# Qwiic-OpenLog.net
KiCad netlist of a schematic drawn in EAGLE
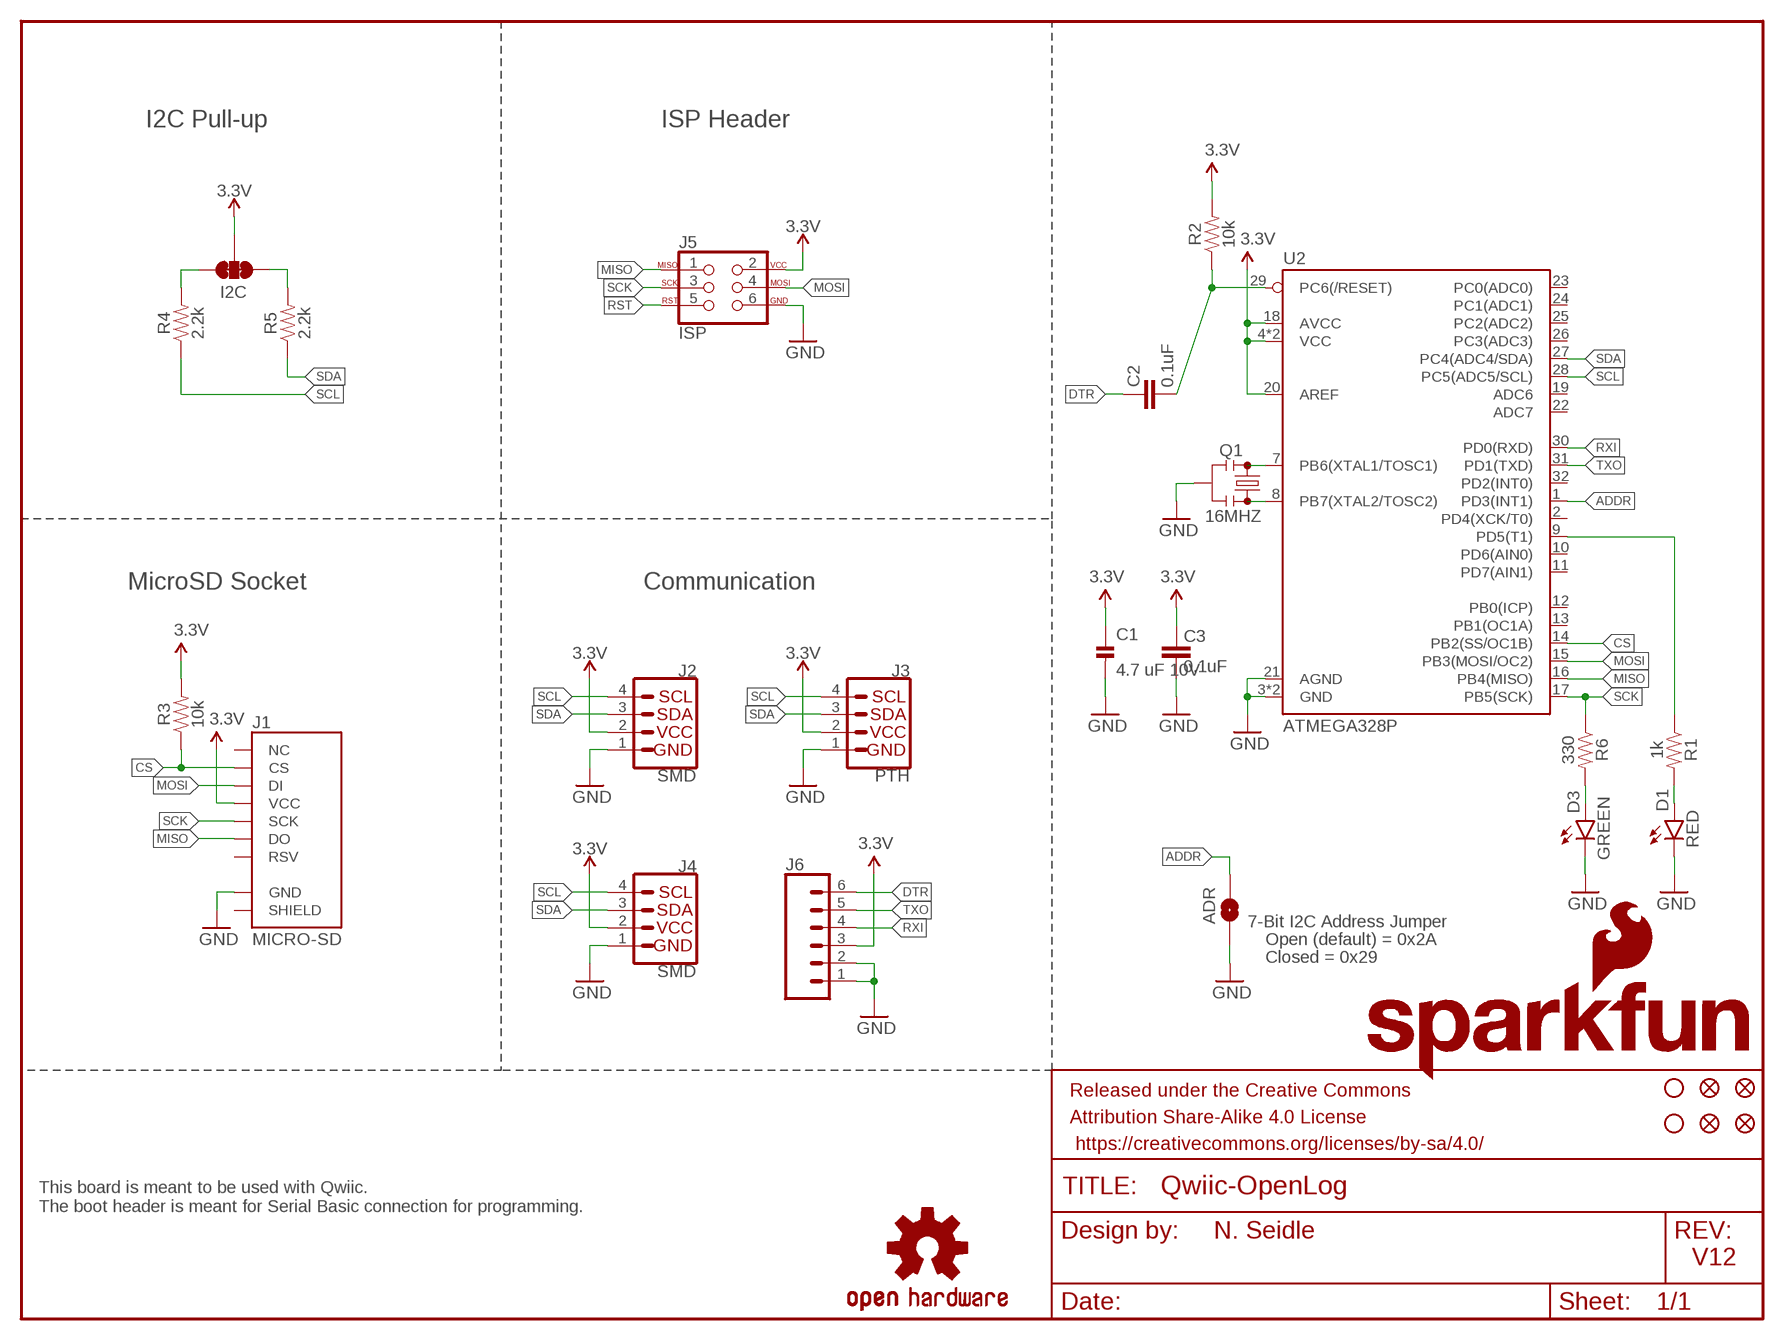
[diagram p0: schematic, sheet 1]

(export (version "E")
  (design (tool "Eeschema 10.0.6"))
  (components
    (comp (ref "ADR")
      (value "SOLDERJUMPERNO")
      (footprint "eagle-import:SJ_2S-NO")
      (libsource (lib "eagle-import") (part "SOLDERJUMPERNO"))
    )
    (comp (ref "C1")
      (value "4.7 uF 10V")
      (footprint "eagle-import:C0805")
      (fields (field (name "MANUFACTURER") "KEMET") (field (name "MPN") "C0805C475J8RACAUTO"))
      (libsource (lib "eagle-import") (part "C0805C475J8RACAUTO"))
    )
    (comp (ref "C2")
      (value "0.1uF")
      (footprint "eagle-import:0603")
      (libsource (lib "eagle-import") (part "0.1UF-0603-25V-(+80/-20%)"))
    )
    (comp (ref "C3")
      (value "0.1uF")
      (footprint "eagle-import:0603")
      (libsource (lib "eagle-import") (part "0.1UF-0603-25V-(+80/-20%)"))
    )
    (comp (ref "D1")
      (value "RED")
      (footprint "eagle-import:LED-0603")
      (libsource (lib "eagle-import") (part "LED-RED0603"))
    )
    (comp (ref "D3")
      (value "GREEN")
      (footprint "eagle-import:LED-0603")
      (libsource (lib "eagle-import") (part "LED-GREEN0603"))
    )
    (comp (ref "FID1")
      (value "FIDUCIALUFIDUCIAL")
      (footprint "eagle-import:FIDUCIAL-MICRO")
      (libsource (lib "eagle-import") (part "FIDUCIALUFIDUCIAL"))
    )
    (comp (ref "FID2")
      (value "FIDUCIALUFIDUCIAL")
      (footprint "eagle-import:FIDUCIAL-MICRO")
      (libsource (lib "eagle-import") (part "FIDUCIALUFIDUCIAL"))
    )
    (comp (ref "FID3")
      (value "FIDUCIALUFIDUCIAL")
      (footprint "eagle-import:FIDUCIAL-MICRO")
      (libsource (lib "eagle-import") (part "FIDUCIALUFIDUCIAL"))
    )
    (comp (ref "FID4")
      (value "FIDUCIALUFIDUCIAL")
      (footprint "eagle-import:FIDUCIAL-MICRO")
      (libsource (lib "eagle-import") (part "FIDUCIALUFIDUCIAL"))
    )
    (comp (ref "FRAME1")
      (value "FRAME-LETTER")
      (footprint "eagle-import:CREATIVE_COMMONS")
      (libsource (lib "eagle-import") (part "FRAME-LETTER"))
    )
    (comp (ref "I2C")
      (value "JUMPER-SMT_3_2-NC_TRACE_SILK")
      (footprint "eagle-import:SMT-JUMPER_3_2-NC_TRACE_SILK")
      (libsource (lib "eagle-import") (part "JUMPER-SMT_3_2-NC_TRACE_SILK"))
    )
    (comp (ref "J1")
      (value "MICRO-SD")
      (footprint "eagle-import:MICRO-SD-SOCKET")
      (libsource (lib "eagle-import") (part "MICRO-SD_CARD_SOCKETPUSH-PUSH"))
    )
    (comp (ref "J2")
      (value "SMD")
      (footprint "eagle-import:1X04_1MM_RA")
      (libsource (lib "eagle-import") (part "QWIIC_CONNECTORJS-1MM"))
    )
    (comp (ref "J3")
      (value "PTH")
      (footprint "eagle-import:1X04_NO_SILK")
      (libsource (lib "eagle-import") (part "I2C_STANDARD_NO_SILK"))
    )
    (comp (ref "J4")
      (value "SMD")
      (footprint "eagle-import:1X04_1MM_RA")
      (libsource (lib "eagle-import") (part "QWIIC_CONNECTORJS-1MM"))
    )
    (comp (ref "J5")
      (value "ISP")
      (footprint "eagle-import:2X3_TEST_POINTS")
      (libsource (lib "eagle-import") (part "AVR_SPI_PROG_3X2TESTPOINTS"))
    )
    (comp (ref "J6")
      (value "CONN_06NO_SILK_NO_POP")
      (footprint "eagle-import:1X06_NO_SILK")
      (libsource (lib "eagle-import") (part "CONN_06NO_SILK_NO_POP"))
    )
    (comp (ref "JP3")
      (value "STAND-OFF")
      (footprint "eagle-import:STAND-OFF")
      (libsource (lib "eagle-import") (part "STAND-OFF"))
    )
    (comp (ref "JP4")
      (value "STAND-OFF")
      (footprint "eagle-import:STAND-OFF")
      (libsource (lib "eagle-import") (part "STAND-OFF"))
    )
    (comp (ref "LOGO1")
      (value "SFE_LOGO_FLAME.1_INCH")
      (footprint "eagle-import:SFE_LOGO_FLAME_.1")
      (libsource (lib "eagle-import") (part "SFE_LOGO_FLAME.1_INCH"))
    )
    (comp (ref "LOGO2")
      (value "OSHW-LOGOMINI")
      (footprint "eagle-import:OSHW-LOGO-MINI")
      (libsource (lib "eagle-import") (part "OSHW-LOGOMINI"))
    )
    (comp (ref "LOGO4")
      (value "SFE_LOGO_NAME_FLAME.1_INCH")
      (footprint "eagle-import:SFE_LOGO_NAME_FLAME_.1")
      (libsource (lib "eagle-import") (part "SFE_LOGO_NAME_FLAME.1_INCH"))
    )
    (comp (ref "Q1")
      (value "16MHZ")
      (footprint "eagle-import:RESONATOR-SMD")
      (libsource (lib "eagle-import") (part "RESONATOR16MHZ"))
    )
    (comp (ref "R1")
      (value "1k")
      (footprint "eagle-import:0603")
      (libsource (lib "eagle-import") (part "1KOHM-0603-1/10W-1%"))
    )
    (comp (ref "R2")
      (value "10k")
      (footprint "eagle-import:0603")
      (libsource (lib "eagle-import") (part "10KOHM-0603-1/10W-1%"))
    )
    (comp (ref "R3")
      (value "10k")
      (footprint "eagle-import:0603")
      (libsource (lib "eagle-import") (part "10KOHM-0603-1/10W-1%"))
    )
    (comp (ref "R4")
      (value "2.2k")
      (footprint "eagle-import:0603")
      (libsource (lib "eagle-import") (part "2.2KOHM-0603-1/10W-1%"))
    )
    (comp (ref "R5")
      (value "2.2k")
      (footprint "eagle-import:0603")
      (libsource (lib "eagle-import") (part "2.2KOHM-0603-1/10W-1%"))
    )
    (comp (ref "R6")
      (value "330")
      (footprint "eagle-import:0603")
      (libsource (lib "eagle-import") (part "330OHM-0603-1/10W-1%"))
    )
    (comp (ref "U2")
      (value "ATMEGA328P")
      (footprint "eagle-import:TQFP32-08")
      (libsource (lib "eagle-import") (part "ATMEGA328P_TQFP"))
    )
  )
  (nets
    (net (code "1") (name "3.3V") (class "Default")
      (node (ref "C1") (pin "1") (pinfunction "1_1") (pintype "passive"))
      (node (ref "C3") (pin "2") (pinfunction "2_2") (pintype "passive"))
      (node (ref "I2C") (pin "2") (pinfunction "2_2") (pintype "passive"))
      (node (ref "J1") (pin "VCC") (pinfunction "VCC_VCC") (pintype "bidirectional"))
      (node (ref "J2") (pin "2") (pinfunction "2_2") (pintype "power_in"))
      (node (ref "J3") (pin "2") (pinfunction "VCC_2") (pintype "power_in"))
      (node (ref "J4") (pin "2") (pinfunction "2_2") (pintype "power_in"))
      (node (ref "J5") (pin "2") (pinfunction "2_2") (pintype "passive"))
      (node (ref "J6") (pin "3") (pinfunction "3_3") (pintype "passive"))
      (node (ref "R2") (pin "2") (pinfunction "2_2") (pintype "passive"))
      (node (ref "R3") (pin "2") (pinfunction "2_2") (pintype "passive"))
      (node (ref "U2") (pin "18") (pinfunction "AVCC_18") (pintype "bidirectional"))
      (node (ref "U2") (pin "20") (pinfunction "AREF_20") (pintype "bidirectional"))
      (node (ref "U2") (pin "4") (pinfunction "VCC_4") (pintype "bidirectional"))
      (node (ref "U2") (pin "6") (pinfunction "VCC_6") (pintype "bidirectional"))
    )
    (net (code "2") (name "ADDR") (class "Default")
      (node (ref "ADR") (pin "2") (pinfunction "2_2") (pintype "passive"))
      (node (ref "U2") (pin "1") (pinfunction "PD3(INT1)_1") (pintype "bidirectional"))
    )
    (net (code "3") (name "CS") (class "Default")
      (node (ref "J1") (pin "CS") (pinfunction "CS_CS") (pintype "bidirectional"))
      (node (ref "R3") (pin "1") (pinfunction "1_1") (pintype "passive"))
      (node (ref "U2") (pin "14") (pinfunction "PB2(SS/OC1B)_14") (pintype "bidirectional"))
    )
    (net (code "4") (name "DTR") (class "Default")
      (node (ref "C2") (pin "2") (pinfunction "2_2") (pintype "passive"))
      (node (ref "J6") (pin "6") (pinfunction "6_6") (pintype "passive"))
    )
    (net (code "5") (name "GND") (class "Default")
      (node (ref "ADR") (pin "1") (pinfunction "1_1") (pintype "passive"))
      (node (ref "C1") (pin "2") (pinfunction "2_2") (pintype "passive"))
      (node (ref "C3") (pin "1") (pinfunction "1_1") (pintype "passive"))
      (node (ref "D1") (pin "C") (pinfunction "C_C") (pintype "passive"))
      (node (ref "D3") (pin "C") (pinfunction "C_C") (pintype "passive"))
      (node (ref "J1") (pin "GND") (pinfunction "GND_GND") (pintype "bidirectional"))
      (node (ref "J2") (pin "1") (pinfunction "1_1") (pintype "power_in"))
      (node (ref "J3") (pin "1") (pinfunction "GND_1") (pintype "power_in"))
      (node (ref "J4") (pin "1") (pinfunction "1_1") (pintype "power_in"))
      (node (ref "J5") (pin "6") (pinfunction "6_6") (pintype "passive"))
      (node (ref "J6") (pin "1") (pinfunction "1_1") (pintype "passive"))
      (node (ref "J6") (pin "2") (pinfunction "2_2") (pintype "passive"))
      (node (ref "Q1") (pin "2") (pinfunction "2_2") (pintype "passive"))
      (node (ref "U2") (pin "21") (pinfunction "AGND_21") (pintype "bidirectional"))
      (node (ref "U2") (pin "3") (pinfunction "GND_3") (pintype "bidirectional"))
      (node (ref "U2") (pin "5") (pinfunction "GND_5") (pintype "bidirectional"))
    )
    (net (code "6") (name "MISO") (class "Default")
      (node (ref "J1") (pin "DO") (pinfunction "DO_DO") (pintype "bidirectional"))
      (node (ref "J5") (pin "1") (pinfunction "1_1") (pintype "passive"))
      (node (ref "U2") (pin "16") (pinfunction "PB4(MISO)_16") (pintype "bidirectional"))
    )
    (net (code "7") (name "MOSI") (class "Default")
      (node (ref "J1") (pin "DI") (pinfunction "DI_DI") (pintype "bidirectional"))
      (node (ref "J5") (pin "4") (pinfunction "4_4") (pintype "passive"))
      (node (ref "U2") (pin "15") (pinfunction "PB3(MOSI/OC2)_15") (pintype "bidirectional"))
    )
    (net (code "8") (name "Net-(D1-PadA)") (class "Default")
      (node (ref "D1") (pin "A") (pinfunction "A_A") (pintype "passive"))
      (node (ref "R1") (pin "2") (pinfunction "2_2") (pintype "passive"))
    )
    (net (code "9") (name "Net-(D3-PadA)") (class "Default")
      (node (ref "D3") (pin "A") (pinfunction "A_A") (pintype "passive"))
      (node (ref "R6") (pin "2") (pinfunction "2_2") (pintype "passive"))
    )
    (net (code "10") (name "Net-(I2C-Pad1)") (class "Default")
      (node (ref "I2C") (pin "1") (pinfunction "1_1") (pintype "passive"))
      (node (ref "R5") (pin "2") (pinfunction "2_2") (pintype "passive"))
    )
    (net (code "11") (name "Net-(I2C-Pad3)") (class "Default")
      (node (ref "I2C") (pin "3") (pinfunction "3_3") (pintype "passive"))
      (node (ref "R4") (pin "2") (pinfunction "2_2") (pintype "passive"))
    )
    (net (code "12") (name "Net-(U2-PB6(XTAL1{slash}TOSC1))") (class "Default")
      (node (ref "Q1") (pin "3") (pinfunction "3_3") (pintype "passive"))
      (node (ref "U2") (pin "7") (pinfunction "PB6(XTAL1/TOSC1)_7") (pintype "bidirectional"))
    )
    (net (code "13") (name "Net-(U2-PB7(XTAL2{slash}TOSC2))") (class "Default")
      (node (ref "Q1") (pin "1") (pinfunction "1_1") (pintype "passive"))
      (node (ref "U2") (pin "8") (pinfunction "PB7(XTAL2/TOSC2)_8") (pintype "bidirectional"))
    )
    (net (code "14") (name "Net-(U2-PD5(T1))") (class "Default")
      (node (ref "R1") (pin "1") (pinfunction "1_1") (pintype "passive"))
      (node (ref "U2") (pin "9") (pinfunction "PD5(T1)_9") (pintype "bidirectional"))
    )
    (net (code "15") (name "RST") (class "Default")
      (node (ref "C2") (pin "1") (pinfunction "1_1") (pintype "passive"))
      (node (ref "J5") (pin "5") (pinfunction "5_5") (pintype "passive"))
      (node (ref "R2") (pin "1") (pinfunction "1_1") (pintype "passive"))
      (node (ref "U2") (pin "29") (pinfunction "PC6(/RESET)_29") (pintype "bidirectional"))
    )
    (net (code "16") (name "RXI") (class "Default")
      (node (ref "J6") (pin "4") (pinfunction "4_4") (pintype "passive"))
      (node (ref "U2") (pin "30") (pinfunction "PD0(RXD)_30") (pintype "bidirectional"))
    )
    (net (code "17") (name "SCK") (class "Default")
      (node (ref "J1") (pin "SCLK") (pinfunction "SCK_SCLK") (pintype "bidirectional"))
      (node (ref "J5") (pin "3") (pinfunction "3_3") (pintype "passive"))
      (node (ref "R6") (pin "1") (pinfunction "1_1") (pintype "passive"))
      (node (ref "U2") (pin "17") (pinfunction "PB5(SCK)_17") (pintype "bidirectional"))
    )
    (net (code "18") (name "SCL") (class "Default")
      (node (ref "J2") (pin "4") (pinfunction "4_4") (pintype "passive"))
      (node (ref "J3") (pin "4") (pinfunction "SCL_4") (pintype "passive"))
      (node (ref "J4") (pin "4") (pinfunction "4_4") (pintype "passive"))
      (node (ref "R4") (pin "1") (pinfunction "1_1") (pintype "passive"))
      (node (ref "U2") (pin "28") (pinfunction "PC5(ADC5/SCL)_28") (pintype "bidirectional"))
    )
    (net (code "19") (name "SDA") (class "Default")
      (node (ref "J2") (pin "3") (pinfunction "3_3") (pintype "passive"))
      (node (ref "J3") (pin "3") (pinfunction "SDA_3") (pintype "passive"))
      (node (ref "J4") (pin "3") (pinfunction "3_3") (pintype "passive"))
      (node (ref "R5") (pin "1") (pinfunction "1_1") (pintype "passive"))
      (node (ref "U2") (pin "27") (pinfunction "PC4(ADC4/SDA)_27") (pintype "bidirectional"))
    )
    (net (code "20") (name "TXO") (class "Default")
      (node (ref "J6") (pin "5") (pinfunction "5_5") (pintype "passive"))
      (node (ref "U2") (pin "31") (pinfunction "PD1(TXD)_31") (pintype "bidirectional"))
    )
    (net (code "21") (name "unconnected-(J1-NC-PadRSV2)") (class "Default")
      (node (ref "J1") (pin "RSV2") (pinfunction "NC_RSV2") (pintype "bidirectional"))
    )
    (net (code "22") (name "unconnected-(J1-RSV-PadRSV1)") (class "Default")
      (node (ref "J1") (pin "RSV1") (pinfunction "RSV_RSV1") (pintype "bidirectional"))
    )
    (net (code "23") (name "unconnected-(J1-SHIELD-PadCD1)") (class "Default")
      (node (ref "J1") (pin "CD1") (pinfunction "SHIELD_CD1") (pintype "bidirectional"))
    )
    (net (code "24") (name "unconnected-(U2-ADC6-Pad19)") (class "Default")
      (node (ref "U2") (pin "19") (pinfunction "ADC6_19") (pintype "bidirectional"))
    )
    (net (code "25") (name "unconnected-(U2-ADC7-Pad22)") (class "Default")
      (node (ref "U2") (pin "22") (pinfunction "ADC7_22") (pintype "bidirectional"))
    )
    (net (code "26") (name "unconnected-(U2-PB0(ICP)-Pad12)") (class "Default")
      (node (ref "U2") (pin "12") (pinfunction "PB0(ICP)_12") (pintype "bidirectional"))
    )
    (net (code "27") (name "unconnected-(U2-PB1(OC1A)-Pad13)") (class "Default")
      (node (ref "U2") (pin "13") (pinfunction "PB1(OC1A)_13") (pintype "bidirectional"))
    )
    (net (code "28") (name "unconnected-(U2-PC0(ADC0)-Pad23)") (class "Default")
      (node (ref "U2") (pin "23") (pinfunction "PC0(ADC0)_23") (pintype "bidirectional"))
    )
    (net (code "29") (name "unconnected-(U2-PC1(ADC1)-Pad24)") (class "Default")
      (node (ref "U2") (pin "24") (pinfunction "PC1(ADC1)_24") (pintype "bidirectional"))
    )
    (net (code "30") (name "unconnected-(U2-PC2(ADC2)-Pad25)") (class "Default")
      (node (ref "U2") (pin "25") (pinfunction "PC2(ADC2)_25") (pintype "bidirectional"))
    )
    (net (code "31") (name "unconnected-(U2-PC3(ADC3)-Pad26)") (class "Default")
      (node (ref "U2") (pin "26") (pinfunction "PC3(ADC3)_26") (pintype "bidirectional"))
    )
    (net (code "32") (name "unconnected-(U2-PD2(INT0)-Pad32)") (class "Default")
      (node (ref "U2") (pin "32") (pinfunction "PD2(INT0)_32") (pintype "bidirectional"))
    )
    (net (code "33") (name "unconnected-(U2-PD4(XCK{slash}T0)-Pad2)") (class "Default")
      (node (ref "U2") (pin "2") (pinfunction "PD4(XCK/T0)_2") (pintype "bidirectional"))
    )
    (net (code "34") (name "unconnected-(U2-PD6(AIN0)-Pad10)") (class "Default")
      (node (ref "U2") (pin "10") (pinfunction "PD6(AIN0)_10") (pintype "bidirectional"))
    )
    (net (code "35") (name "unconnected-(U2-PD7(AIN1)-Pad11)") (class "Default")
      (node (ref "U2") (pin "11") (pinfunction "PD7(AIN1)_11") (pintype "bidirectional"))
    )
  )
)
